# DRA818V_transceiver_module.net
KiCad netlist of a schematic drawn in Altium Designer
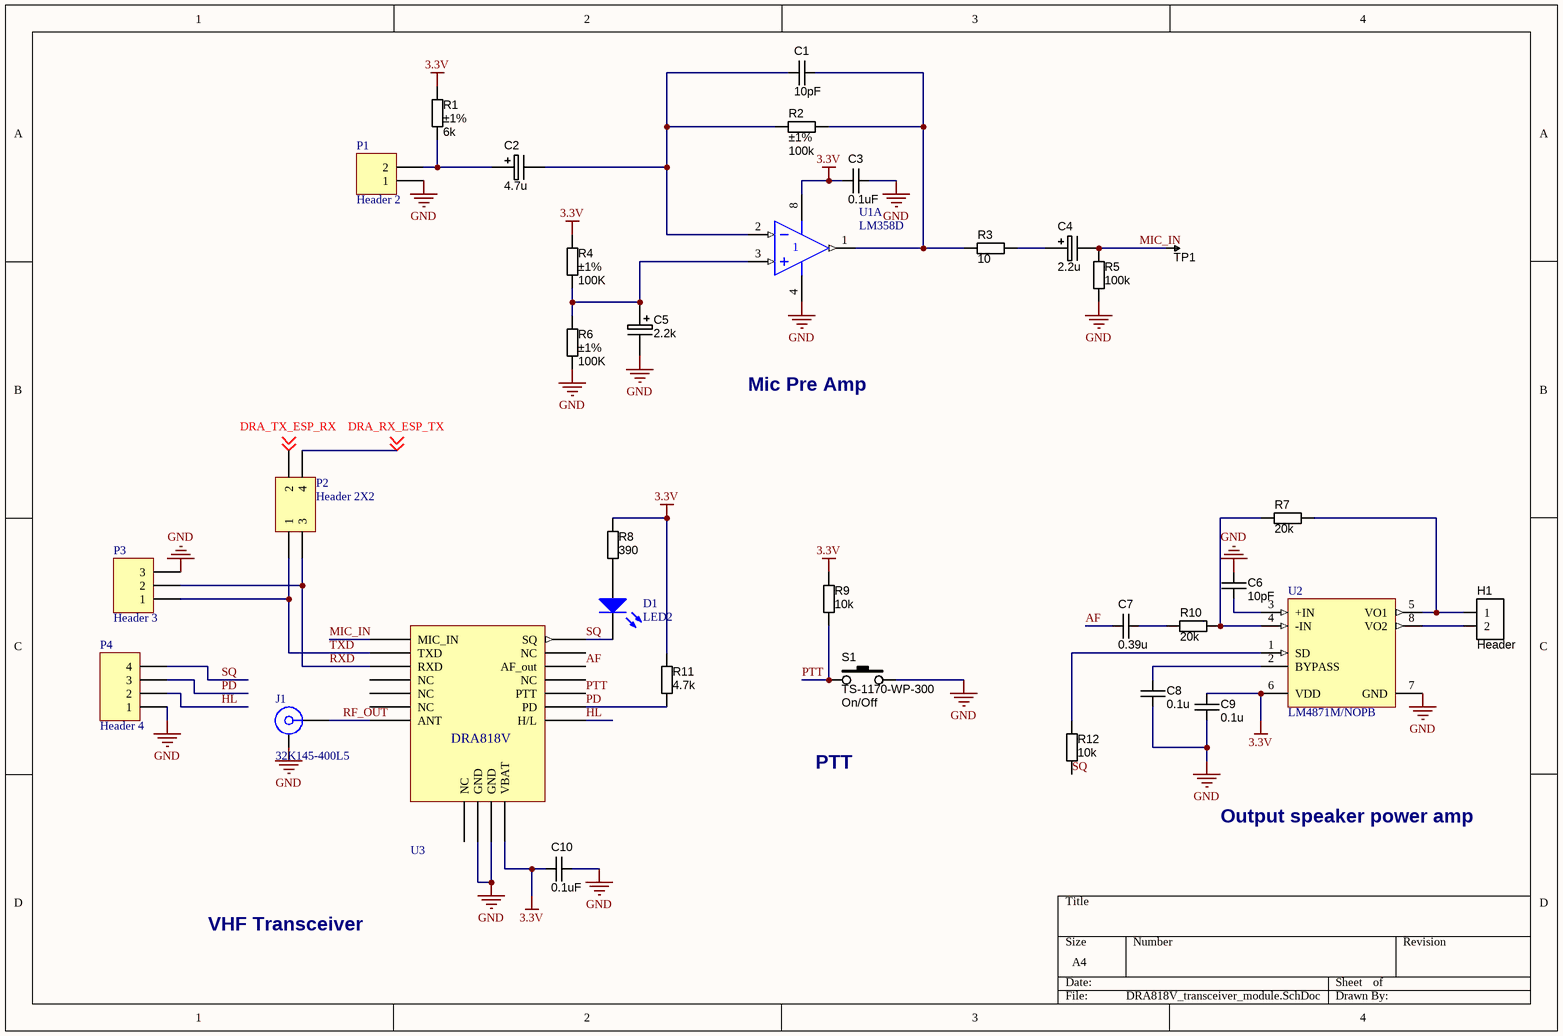
[diagram p0: DRA818V_transceiver_module.SchDoc]

(export (version "E")
  (design (tool "Eeschema 10.0.6"))
  (components
    (comp (ref "C1")
      (value "10pF")
      (footprint "CAPC2012X135N")
      (description "Capacitor SMD Cer 100nF 10% 100V X7R 0805")
      (fields (field (name "TOLERANCE") "±10%") (field (name "Comment") "approved sub OK"))
      (libsource (lib "PBL - Capacitors") (part "CAPC_100n_0805_X7R_100V_10%"))
    )
    (comp (ref "C2")
      (value "4.7u")
      (footprint "CAPMP3216X180N")
      (description "Capacitor SMD Tantalum 33uF 10% 6.3V 3216-18")
      (fields (field (name "TOLERANCE") "±10%"))
      (libsource (lib "PBL - Capacitors") (part "CAPT_33u_3216_6V3"))
    )
    (comp (ref "C3")
      (value "0.1uF")
      (footprint "CAPC2012X135N")
      (description "Capacitor SMD Cer 100nF 10% 100V X7R 0805")
      (fields (field (name "TOLERANCE") "±10%") (field (name "Comment") "approved sub OK"))
      (libsource (lib "PBL - Capacitors") (part "CAPC_100n_0805_X7R_100V_10%"))
    )
    (comp (ref "C4")
      (value "2.2u")
      (footprint "CAPMP3216X180N")
      (description "Capacitor SMD Tantalum 33uF 10% 6.3V 3216-18")
      (fields (field (name "TOLERANCE") "±10%"))
      (libsource (lib "PBL - Capacitors") (part "CAPT_33u_3216_6V3"))
    )
    (comp (ref "C5")
      (value "2.2k")
      (footprint "CAPMP3216X180N")
      (description "Capacitor SMD Tantalum 33uF 10% 6.3V 3216-18")
      (fields (field (name "TOLERANCE") "±10%"))
      (libsource (lib "PBL - Capacitors") (part "CAPT_33u_3216_6V3"))
    )
    (comp (ref "C6")
      (value "10pF")
      (footprint "CAPC2012X135N")
      (description "Capacitor SMD Cer 100nF 10% 100V X7R 0805")
      (fields (field (name "TOLERANCE") "±10%") (field (name "Comment") "approved sub OK"))
      (libsource (lib "PBL - Capacitors") (part "CAPC_100n_0805_X7R_100V_10%"))
    )
    (comp (ref "C7")
      (value "0.39u")
      (footprint "CAPC2012X135N")
      (description "Capacitor SMD Cer 100nF 10% 100V X7R 0805")
      (fields (field (name "TOLERANCE") "±10%") (field (name "Comment") "approved sub OK"))
      (libsource (lib "PBL - Capacitors") (part "CAPC_100n_0805_X7R_100V_10%"))
    )
    (comp (ref "C8")
      (value "0.1u")
      (footprint "CAPC2012X135N")
      (description "Capacitor SMD Cer 100nF 10% 100V X7R 0805")
      (fields (field (name "TOLERANCE") "±10%") (field (name "Comment") "approved sub OK"))
      (libsource (lib "PBL - Capacitors") (part "CAPC_100n_0805_X7R_100V_10%"))
    )
    (comp (ref "C9")
      (value "0.1u")
      (footprint "CAPC2012X135N")
      (description "Capacitor SMD Cer 100nF 10% 100V X7R 0805")
      (fields (field (name "TOLERANCE") "±10%") (field (name "Comment") "approved sub OK"))
      (libsource (lib "PBL - Capacitors") (part "CAPC_100n_0805_X7R_100V_10%"))
    )
    (comp (ref "C10")
      (value "0.1uF")
      (footprint "CAPC2012X135N")
      (description "Capacitor SMD Cer 100nF 10% 100V X7R 0805")
      (fields (field (name "TOLERANCE") "±10%") (field (name "Comment") "approved sub OK"))
      (libsource (lib "PBL - Capacitors") (part "CAPC_100n_0805_X7R_100V_10%"))
    )
    (comp (ref "D1")
      (value "LED2")
      (footprint "3.2X1.6X1.1")
      (description "Typical RED, GREEN, YELLOW, AMBER GaAs LED")
      (fields (field (name "PUBLISHER") "Altium Limited"))
      (libsource (lib "Miscellaneous Devices") (part "LED2"))
    )
    (comp (ref "H1")
      (value "Header")
      (footprint "HDR_1x2_Offset")
      (description "Header, 2-pin")
      (libsource (lib "PBL - Connectors") (part "Header2P"))
    )
    (comp (ref "J1")
      (value "32K145-400L5")
      (footprint "ROS-32K145-400L5_V")
      (description "SMA Right Angle Jack, Edge Mount, Up to 18 GHz, -55 to 155 degC")
      (libsource (lib "Rosenberger SMA") (part "32K145-400L5"))
    )
    (comp (ref "P1")
      (value "Header 2")
      (footprint "HDR1X2")
      (description "Header, 2-Pin")
      (fields (field (name "PUBLISHER") "Altium Limited"))
      (libsource (lib "Miscellaneous Connectors") (part "Header 2"))
    )
    (comp (ref "P2")
      (value "Header 2X2")
      (footprint "HDR2X2")
      (description "Header, 2-Pin, Dual row")
      (fields (field (name "PUBLISHER") "Altium Limited"))
      (libsource (lib "Miscellaneous Connectors") (part "Header 2X2"))
    )
    (comp (ref "P3")
      (value "Header 3")
      (footprint "HDR1X3")
      (description "Header, 3-Pin")
      (fields (field (name "PUBLISHER") "Altium Limited"))
      (libsource (lib "Miscellaneous Connectors") (part "Header 3"))
    )
    (comp (ref "P4")
      (value "Header 4")
      (footprint "HDR1X4")
      (description "Header, 4-Pin")
      (fields (field (name "PUBLISHER") "Altium Limited"))
      (libsource (lib "Miscellaneous Connectors") (part "Header 4"))
    )
    (comp (ref "R1")
      (value "6k")
      (footprint "ERA-0805")
      (description "Resistor SMD chip 1.3k Ohm 0.125W 1% 0805")
      (fields (field (name "TOLERANCE") "±1%") (field (name "Comment") "Thick Film"))
      (libsource (lib "PBL - Resistors") (part "RES_1K3_0805_1%"))
    )
    (comp (ref "R2")
      (value "100k")
      (footprint "ERA-0805")
      (description "Resistor SMD chip 7.87k Ohm 0.125W 1% 0805")
      (fields (field (name "TOLERANCE") "±1%") (field (name "Comment") "Thick Film"))
      (libsource (lib "PBL - Resistors") (part "RES_7K87_0805_1%"))
    )
    (comp (ref "R3")
      (value "10")
      (footprint "ERA-0805")
      (description "Resistor SMD chip 0.0 Ohm 0.125W 0805")
      (fields (field (name "Comment") "Jumper"))
      (libsource (lib "") (part "RES_0R_0805_1"))
    )
    (comp (ref "R4")
      (value "100K")
      (footprint "ERA-0805")
      (description "Resistor SMD chip 100k Ohm 0.125W 1% 0805")
      (fields (field (name "TOLERANCE") "±1%") (field (name "Comment") "Thick Film"))
      (libsource (lib "PBL - Resistors") (part "RES_100K_0805_1%"))
    )
    (comp (ref "R5")
      (value "100k")
      (footprint "6-0805")
      (description "Resistor SMD chip 0.0 Ohm 0.125W 0805")
      (fields (field (name "Comment") "Jumper"))
      (libsource (lib "PBL - Resistors") (part "RES_0R_0805"))
    )
    (comp (ref "R6")
      (value "100K")
      (footprint "ERA-0805")
      (description "Resistor SMD chip 100k Ohm 0.125W 1% 0805")
      (fields (field (name "TOLERANCE") "±1%") (field (name "Comment") "Thick Film"))
      (libsource (lib "PBL - Resistors") (part "RES_100K_0805_1%"))
    )
    (comp (ref "R7")
      (value "20k")
      (footprint "ERA-0805")
      (description "Resistor SMD chip 0.0 Ohm 0.125W 0805")
      (fields (field (name "Comment") "Jumper"))
      (libsource (lib "") (part "RES_0R_0805_1"))
    )
    (comp (ref "R8")
      (value "390")
      (footprint "ERA-0805")
      (description "Resistor SMD chip 0.0 Ohm 0.125W 0805")
      (fields (field (name "Comment") "Jumper"))
      (libsource (lib "") (part "RES_0R_0805_2"))
    )
    (comp (ref "R9")
      (value "10k")
      (footprint "ERA-0805")
      (description "Resistor SMD chip 0.0 Ohm 0.125W 0805")
      (fields (field (name "Comment") "Jumper"))
      (libsource (lib "PBL - Resistors") (part "RES_0R_0805"))
    )
    (comp (ref "R10")
      (value "20k")
      (footprint "ERA-0805")
      (description "Resistor SMD chip 0.0 Ohm 0.125W 0805")
      (fields (field (name "Comment") "Jumper"))
      (libsource (lib "") (part "RES_0R_0805_1"))
    )
    (comp (ref "R11")
      (value "4.7k")
      (footprint "ERA-0805")
      (description "Resistor SMD chip 0.0 Ohm 0.125W 0805")
      (fields (field (name "Comment") "Jumper"))
      (libsource (lib "PBL - Resistors") (part "RES_0R_0805"))
    )
    (comp (ref "R12")
      (value "10k")
      (footprint "ERA-0805")
      (description "Resistor SMD chip 0.0 Ohm 0.125W 0805")
      (fields (field (name "Comment") "Jumper"))
      (libsource (lib "PBL - Resistors") (part "RES_0R_0805"))
    )
    (comp (ref "S1")
      (value "SW_THT_PB_7.0mm")
      (footprint "TACT-SWITCH-TS1170")
      (description "Switch, tact, 7.0mm stem")
      (fields (field (name "MANUFACTURER PART NUMBER 1") "TS-1170-WP-300") (field (name "FUNCTION") "On/Off"))
      (libsource (lib "PBL - Switches") (part "SW_THT_PB_7.0mm"))
    )
    (comp (ref "TP1")
      (value "TESTPOINT")
      (footprint "TP-R60")
      (description "SMD test pin")
      (libsource (lib "PBL - Test Points") (part "TESTPOINT"))
    )
    (comp (ref "U1")
      (value "LM358D")
      (footprint "751-02_N")
      (description "Dual Low-Power Operational Amplifier")
      (fields (field (name "PUBLISHER") "Altium Limited"))
      (libsource (lib "Motorola Amplifier Operational Amplifier") (part "LM358D"))
    )
    (comp (ref "U2")
      (value "LM4871M/NOPB")
      (footprint "M08A_N")
      (description "3W Audio Power Amplifier with Shutdown Mode, 8-pin Narrow SOIC, Pb-Free")
      (fields
        (field (name "MANUFACTURER") "National Semiconductor")
        (field (name "PUBLISHER") "Altium Limited")
      )
      (libsource (lib "NSC Audio") (part "LM4871M/NOPB"))
    )
    (comp (ref "U3")
      (value "DRA818V")
      (footprint "DRA818_breakout")
      (libsource (lib "DRA818V") (part "DRA818V"))
    )
  )
  (nets
    (net (code "1") (name "/AF") (class "Default")
      (node (ref "C7") (pin "1") (pintype "passive"))
      (node (ref "U3") (pin "3") (pinfunction "AF_out_3") (pintype "passive"))
    )
    (net (code "2") (name "/HL") (class "Default")
      (node (ref "P4") (pin "2") (pinfunction "2_2") (pintype "passive"))
      (node (ref "U3") (pin "7") (pinfunction "H/L_7") (pintype "passive"))
    )
    (net (code "3") (name "/MIC_IN") (class "Default")
      (node (ref "C4") (pin "2") (pintype "passive"))
      (node (ref "R5") (pin "1") (pinfunction "1_1") (pintype "passive"))
      (node (ref "TP1") (pin "1") (pintype "passive"))
      (node (ref "U3") (pin "18") (pinfunction "MIC_IN_18") (pintype "passive"))
    )
    (net (code "4") (name "/PD") (class "Default")
      (node (ref "P4") (pin "3") (pinfunction "3_3") (pintype "passive"))
      (node (ref "R11") (pin "2") (pinfunction "2_2") (pintype "passive"))
      (node (ref "U3") (pin "6") (pinfunction "PD_6") (pintype "passive"))
    )
    (net (code "5") (name "/PTT") (class "Default")
      (node (ref "R9") (pin "2") (pinfunction "2_2") (pintype "passive"))
      (node (ref "S1") (pin "1") (pintype "passive"))
      (node (ref "U3") (pin "5") (pinfunction "PTT_5") (pintype "passive"))
    )
    (net (code "6") (name "/RF_OUT") (class "Default")
      (node (ref "J1") (pin "1") (pinfunction "1_1") (pintype "passive"))
      (node (ref "U3") (pin "12") (pinfunction "ANT_12") (pintype "passive"))
    )
    (net (code "7") (name "/RXD") (class "Default")
      (node (ref "P2") (pin "3") (pinfunction "3_3") (pintype "passive"))
      (node (ref "P3") (pin "2") (pinfunction "2_2") (pintype "passive"))
      (node (ref "U3") (pin "16") (pinfunction "RXD_16") (pintype "passive"))
    )
    (net (code "8") (name "/SQ") (class "Default")
      (node (ref "D1") (pin "2") (pinfunction "K_2") (pintype "passive"))
      (node (ref "P4") (pin "4") (pinfunction "4_4") (pintype "passive"))
      (node (ref "R12") (pin "2") (pinfunction "2_2") (pintype "passive"))
      (node (ref "U3") (pin "1") (pinfunction "SQ_1") (pintype "output"))
    )
    (net (code "9") (name "/TXD") (class "Default")
      (node (ref "P2") (pin "1") (pinfunction "1_1") (pintype "passive"))
      (node (ref "P3") (pin "1") (pinfunction "1_1") (pintype "passive"))
      (node (ref "U3") (pin "17") (pinfunction "TXD_17") (pintype "passive"))
    )
    (net (code "10") (name "3.3V") (class "Default")
      (node (ref "C10") (pin "1") (pintype "passive"))
      (node (ref "C3") (pin "1") (pintype "passive"))
      (node (ref "C9") (pin "2") (pintype "passive"))
      (node (ref "R1") (pin "1") (pinfunction "1_1") (pintype "passive"))
      (node (ref "R11") (pin "1") (pinfunction "1_1") (pintype "passive"))
      (node (ref "R4") (pin "1") (pinfunction "1_1") (pintype "passive"))
      (node (ref "R8") (pin "2") (pinfunction "2_2") (pintype "passive"))
      (node (ref "R9") (pin "1") (pinfunction "1_1") (pintype "passive"))
      (node (ref "U1") (pin "8") (pinfunction "V+_8") (pintype "power_in"))
      (node (ref "U2") (pin "6") (pinfunction "VDD_6") (pintype "power_in"))
      (node (ref "U3") (pin "8") (pinfunction "VBAT_8") (pintype "passive"))
    )
    (net (code "11") (name "DRA_RX_ESP_TX") (class "Default")
      (node (ref "P2") (pin "4") (pinfunction "4_4") (pintype "passive"))
    )
    (net (code "12") (name "DRA_TX_ESP_RX") (class "Default")
      (node (ref "P2") (pin "2") (pinfunction "2_2") (pintype "passive"))
    )
    (net (code "13") (name "GND") (class "Default")
      (node (ref "C10") (pin "2") (pintype "passive"))
      (node (ref "C3") (pin "2") (pintype "passive"))
      (node (ref "C5") (pin "2") (pintype "passive"))
      (node (ref "C6") (pin "2") (pintype "passive"))
      (node (ref "C8") (pin "1") (pintype "passive"))
      (node (ref "C9") (pin "1") (pintype "passive"))
      (node (ref "J1") (pin "MP") (pinfunction "MP_MP") (pintype "passive"))
      (node (ref "P1") (pin "1") (pinfunction "1_1") (pintype "passive"))
      (node (ref "P3") (pin "3") (pinfunction "3_3") (pintype "passive"))
      (node (ref "P4") (pin "1") (pinfunction "1_1") (pintype "passive"))
      (node (ref "R5") (pin "2") (pinfunction "2_2") (pintype "passive"))
      (node (ref "R6") (pin "2") (pinfunction "2_2") (pintype "passive"))
      (node (ref "S1") (pin "2") (pintype "passive"))
      (node (ref "U1") (pin "4") (pinfunction "V-_4") (pintype "power_in"))
      (node (ref "U2") (pin "7") (pinfunction "GND_7") (pintype "power_in"))
      (node (ref "U3") (pin "10") (pinfunction "GND_10") (pintype "passive"))
      (node (ref "U3") (pin "9") (pinfunction "GND_9") (pintype "passive"))
    )
    (net (code "14") (name "Net-(C2-Pad1)") (class "Default")
      (node (ref "C2") (pin "1") (pintype "passive"))
      (node (ref "P1") (pin "2") (pinfunction "2_2") (pintype "passive"))
      (node (ref "R1") (pin "2") (pinfunction "2_2") (pintype "passive"))
    )
    (net (code "15") (name "Net-(C4-Pad1)") (class "Default")
      (node (ref "C4") (pin "1") (pintype "passive"))
      (node (ref "R3") (pin "2") (pinfunction "2_2") (pintype "passive"))
    )
    (net (code "16") (name "Net-(C7-Pad2)") (class "Default")
      (node (ref "C7") (pin "2") (pintype "passive"))
      (node (ref "R10") (pin "1") (pinfunction "1_1") (pintype "passive"))
    )
    (net (code "17") (name "Net-(D1-A)") (class "Default")
      (node (ref "D1") (pin "1") (pinfunction "A_1") (pintype "passive"))
      (node (ref "R8") (pin "1") (pinfunction "1_1") (pintype "passive"))
    )
    (net (code "18") (name "Net-(U1A-IN+)") (class "Default")
      (node (ref "C5") (pin "1") (pintype "passive"))
      (node (ref "R4") (pin "2") (pinfunction "2_2") (pintype "passive"))
      (node (ref "R6") (pin "1") (pinfunction "1_1") (pintype "passive"))
      (node (ref "U1") (pin "3") (pinfunction "IN+_3") (pintype "input"))
    )
    (net (code "19") (name "Net-(U1A-IN-)") (class "Default")
      (node (ref "C1") (pin "1") (pintype "passive"))
      (node (ref "C2") (pin "2") (pintype "passive"))
      (node (ref "R2") (pin "1") (pinfunction "1_1") (pintype "passive"))
      (node (ref "U1") (pin "2") (pinfunction "IN-_2") (pintype "input"))
    )
    (net (code "20") (name "Net-(U1A-OUT)") (class "Default")
      (node (ref "C1") (pin "2") (pintype "passive"))
      (node (ref "R2") (pin "2") (pinfunction "2_2") (pintype "passive"))
      (node (ref "R3") (pin "1") (pinfunction "1_1") (pintype "passive"))
      (node (ref "U1") (pin "1") (pinfunction "OUT_1") (pintype "output"))
    )
    (net (code "21") (name "Net-(U2-+IN)") (class "Default")
      (node (ref "C6") (pin "1") (pintype "passive"))
      (node (ref "U2") (pin "3") (pinfunction "+IN_3") (pintype "input"))
    )
    (net (code "22") (name "Net-(U2--IN)") (class "Default")
      (node (ref "R10") (pin "2") (pinfunction "2_2") (pintype "passive"))
      (node (ref "R7") (pin "1") (pinfunction "1_1") (pintype "passive"))
      (node (ref "U2") (pin "4") (pinfunction "-IN_4") (pintype "input"))
    )
    (net (code "23") (name "Net-(U2-BYPASS)") (class "Default")
      (node (ref "C8") (pin "2") (pintype "passive"))
      (node (ref "U2") (pin "2") (pinfunction "BYPASS_2") (pintype "passive"))
    )
    (net (code "24") (name "Net-(U2-SD)") (class "Default")
      (node (ref "R12") (pin "1") (pinfunction "1_1") (pintype "passive"))
      (node (ref "U2") (pin "1") (pinfunction "SD_1") (pintype "input"))
    )
    (net (code "25") (name "Net-(U2-VO1)") (class "Default")
      (node (ref "H1") (pin "1") (pinfunction "1_1") (pintype "passive"))
      (node (ref "R7") (pin "2") (pinfunction "2_2") (pintype "passive"))
      (node (ref "U2") (pin "5") (pinfunction "VO1_5") (pintype "output"))
    )
    (net (code "26") (name "Net-(U2-VO2)") (class "Default")
      (node (ref "H1") (pin "2") (pinfunction "2_2") (pintype "passive"))
      (node (ref "U2") (pin "8") (pinfunction "VO2_8") (pintype "output"))
    )
    (net (code "27") (name "unconnected-(U3-NC-Pad2)") (class "Default")
      (node (ref "U3") (pin "2") (pinfunction "NC_2") (pintype "passive"))
    )
    (net (code "28") (name "unconnected-(U3-NC-Pad4)") (class "Default")
      (node (ref "U3") (pin "4") (pinfunction "NC_4") (pintype "passive"))
    )
    (net (code "29") (name "unconnected-(U3-NC-Pad11)") (class "Default")
      (node (ref "U3") (pin "11") (pinfunction "NC_11") (pintype "passive"))
    )
    (net (code "30") (name "unconnected-(U3-NC-Pad13)") (class "Default")
      (node (ref "U3") (pin "13") (pinfunction "NC_13") (pintype "passive"))
    )
    (net (code "31") (name "unconnected-(U3-NC-Pad14)") (class "Default")
      (node (ref "U3") (pin "14") (pinfunction "NC_14") (pintype "passive"))
    )
    (net (code "32") (name "unconnected-(U3-NC-Pad15)") (class "Default")
      (node (ref "U3") (pin "15") (pinfunction "NC_15") (pintype "passive"))
    )
  )
)
